# Power.net
KiCad netlist of a schematic drawn in Altium Designer
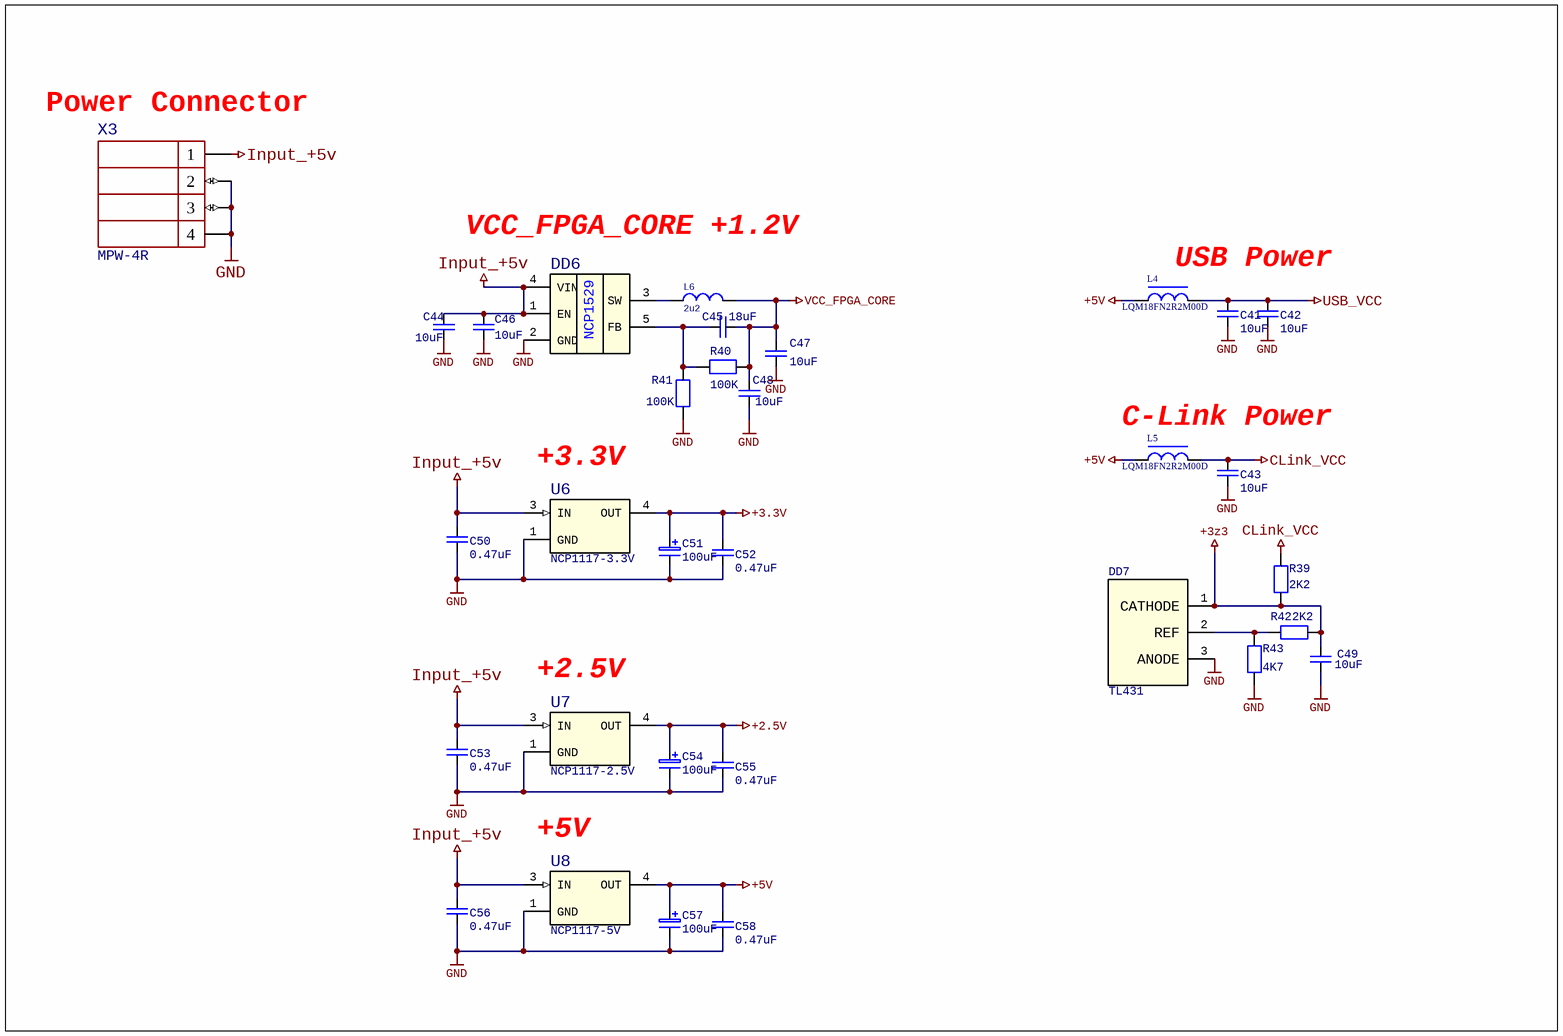
[diagram p0: Power.SchDoc]

(export (version "E")
  (design (tool "Eeschema 10.0.6"))
  (components
    (comp (ref "C41")
      (value "10uF")
      (footprint "Passive:C_0603")
      (description "Non-polarised capacitor")
      (libsource (lib "Passive") (part "C"))
    )
    (comp (ref "C42")
      (value "10uF")
      (footprint "Passive:C_0603")
      (description "Non-polarised capacitor")
      (libsource (lib "Passive") (part "C"))
    )
    (comp (ref "C43")
      (value "10uF")
      (footprint "Passive:C_0603")
      (description "Non-polarised capacitor")
      (libsource (lib "Passive") (part "C"))
    )
    (comp (ref "C44")
      (value "10uF")
      (footprint "Passive:C_0603")
      (description "Non-polarised capacitor")
      (libsource (lib "Passive") (part "C"))
    )
    (comp (ref "C45")
      (value "18uF")
      (footprint "Passive:C_0603")
      (description "Non-polarised capacitor")
      (libsource (lib "Passive") (part "C"))
    )
    (comp (ref "C46")
      (value "10uF")
      (footprint "Passive:C_0603")
      (description "Non-polarised capacitor")
      (libsource (lib "Passive") (part "C"))
    )
    (comp (ref "C47")
      (value "10uF")
      (footprint "Passive:C_0603")
      (description "Non-polarised capacitor")
      (libsource (lib "Passive") (part "C"))
    )
    (comp (ref "C48")
      (value "10uF")
      (footprint "Passive:C_0603")
      (description "Non-polarised capacitor")
      (libsource (lib "Passive") (part "C"))
    )
    (comp (ref "C49")
      (value "10uF")
      (footprint "Passive:C_0603")
      (description "Non-polarised capacitor")
      (libsource (lib "Passive") (part "C"))
    )
    (comp (ref "C50")
      (value "0.47uF")
      (footprint "Passive:C_0603")
      (description "Non-polarised capacitor")
      (libsource (lib "Passive") (part "C"))
    )
    (comp (ref "C51")
      (value "100uF")
      (footprint "Passive:SMD D")
      (description "Polarised capacitor")
      (libsource (lib "Passive") (part "C_polar"))
    )
    (comp (ref "C52")
      (value "0.47uF")
      (footprint "Passive:C_0603")
      (description "Non-polarised capacitor")
      (libsource (lib "Passive") (part "C"))
    )
    (comp (ref "C53")
      (value "0.47uF")
      (footprint "Passive:C_0603")
      (description "Non-polarised capacitor")
      (libsource (lib "Passive") (part "C"))
    )
    (comp (ref "C54")
      (value "100uF")
      (footprint "Passive:SMD D")
      (description "Polarised capacitor")
      (libsource (lib "Passive") (part "C_polar"))
    )
    (comp (ref "C55")
      (value "0.47uF")
      (footprint "Passive:C_0603")
      (description "Non-polarised capacitor")
      (libsource (lib "Passive") (part "C"))
    )
    (comp (ref "C56")
      (value "0.47uF")
      (footprint "Passive:C_0603")
      (description "Non-polarised capacitor")
      (libsource (lib "Passive") (part "C"))
    )
    (comp (ref "C57")
      (value "100uF")
      (footprint "Passive:SMD D")
      (description "Polarised capacitor")
      (libsource (lib "Passive") (part "C_polar"))
    )
    (comp (ref "C58")
      (value "0.47uF")
      (footprint "Passive:C_0603")
      (description "Non-polarised capacitor")
      (libsource (lib "Passive") (part "C"))
    )
    (comp (ref "DD6") (value "NCP1529") (footprint "SOT-23-5") (libsource (lib "Power") (part "NCP1529")))
    (comp (ref "DD7") (value "TL431") (footprint "SOT-23") (libsource (lib "Power") (part "TL431")))
    (comp (ref "L4")
      (value "LQM18FN2R2M00D")
      (footprint "Passive:L_0603")
      (libsource (lib "Passive") (part "L"))
    )
    (comp (ref "L5")
      (value "LQM18FN2R2M00D")
      (footprint "Passive:L_0603")
      (libsource (lib "Passive") (part "L"))
    )
    (comp (ref "L6") (value "2u2") (footprint "Passive:L_1008") (libsource (lib "Passive") (part "L_2")))
    (comp (ref "R39") (value "2K2") (footprint "Passive:R_0603") (libsource (lib "") (part "R_2")))
    (comp (ref "R40") (value "100K") (footprint "Passive:R_0603") (libsource (lib "Passive") (part "R")))
    (comp (ref "R41") (value "100K") (footprint "Passive:R_0603") (libsource (lib "") (part "R_1")))
    (comp (ref "R42") (value "2K2") (footprint "Passive:R_0603") (libsource (lib "Passive") (part "R")))
    (comp (ref "R43") (value "4K7") (footprint "Passive:R_0603") (libsource (lib "") (part "R_1")))
    (comp (ref "U6")
      (value "NCP1117-3.3V")
      (footprint "TO:TO-252")
      (description "1.5 V,1.8 V, 1.9 V, 2.0 V, 2.5 V, 2.85 V, 3.3 V, 5.0 V,12 V")
      (libsource (lib "Device") (part "NCP1117"))
    )
    (comp (ref "U7")
      (value "NCP1117-2.5V")
      (footprint "TO:TO-252")
      (description "1.5 V,1.8 V, 1.9 V, 2.0 V, 2.5 V, 2.85 V, 3.3 V, 5.0 V,12 V")
      (libsource (lib "Device") (part "NCP1117"))
    )
    (comp (ref "U8")
      (value "NCP1117-5V")
      (footprint "TO:TO-252")
      (description "1.5 V,1.8 V, 1.9 V, 2.0 V, 2.5 V, 2.85 V, 3.3 V, 5.0 V,12 V")
      (libsource (lib "Device") (part "NCP1117"))
    )
    (comp (ref "X3")
      (value "MPW-4R")
      (footprint "Connector_Power:MPW-4R")
      (description "Разъемы низковольтного питания")
      (libsource (lib "Power") (part "MPW-4R"))
    )
  )
  (nets
    (net (code "1") (name "+2.5V") (class "Default")
      (node (ref "C54") (pin "1") (pinfunction "1_1") (pintype "passive"))
      (node (ref "C55") (pin "1") (pinfunction "1_1") (pintype "passive"))
      (node (ref "U7") (pin "4") (pinfunction "OUT_4") (pintype "passive"))
    )
    (net (code "2") (name "+3.3V") (class "Default")
      (node (ref "C51") (pin "1") (pinfunction "1_1") (pintype "passive"))
      (node (ref "C52") (pin "1") (pinfunction "1_1") (pintype "passive"))
      (node (ref "U6") (pin "4") (pinfunction "OUT_4") (pintype "passive"))
    )
    (net (code "3") (name "+3z3") (class "Default")
      (node (ref "C49") (pin "1") (pinfunction "1_1") (pintype "passive"))
      (node (ref "DD7") (pin "1") (pinfunction "CATHODE_1") (pintype "passive"))
      (node (ref "R39") (pin "1") (pinfunction "1_1") (pintype "passive"))
      (node (ref "R42") (pin "2") (pinfunction "2_2") (pintype "passive"))
    )
    (net (code "4") (name "+5V") (class "Default")
      (node (ref "C57") (pin "1") (pinfunction "1_1") (pintype "passive"))
      (node (ref "C58") (pin "1") (pinfunction "1_1") (pintype "passive"))
      (node (ref "L4") (pin "1") (pinfunction "1_1") (pintype "passive"))
      (node (ref "L5") (pin "1") (pinfunction "1_1") (pintype "passive"))
      (node (ref "U8") (pin "4") (pinfunction "OUT_4") (pintype "passive"))
    )
    (net (code "5") (name "CLink_VCC") (class "Default")
      (node (ref "C43") (pin "1") (pinfunction "1_1") (pintype "passive"))
      (node (ref "L5") (pin "2") (pinfunction "2_2") (pintype "passive"))
      (node (ref "R39") (pin "2") (pinfunction "2_2") (pintype "passive"))
    )
    (net (code "6") (name "GND") (class "Default")
      (node (ref "C41") (pin "2") (pinfunction "2_2") (pintype "passive"))
      (node (ref "C42") (pin "2") (pinfunction "2_2") (pintype "passive"))
      (node (ref "C43") (pin "2") (pinfunction "2_2") (pintype "passive"))
      (node (ref "C44") (pin "2") (pinfunction "2_2") (pintype "passive"))
      (node (ref "C46") (pin "2") (pinfunction "2_2") (pintype "passive"))
      (node (ref "C47") (pin "1") (pinfunction "1_1") (pintype "passive"))
      (node (ref "C48") (pin "1") (pinfunction "1_1") (pintype "passive"))
      (node (ref "C49") (pin "2") (pinfunction "2_2") (pintype "passive"))
      (node (ref "C50") (pin "2") (pinfunction "2_2") (pintype "passive"))
      (node (ref "C51") (pin "2") (pinfunction "2_2") (pintype "passive"))
      (node (ref "C52") (pin "2") (pinfunction "2_2") (pintype "passive"))
      (node (ref "C53") (pin "2") (pinfunction "2_2") (pintype "passive"))
      (node (ref "C54") (pin "2") (pinfunction "2_2") (pintype "passive"))
      (node (ref "C55") (pin "2") (pinfunction "2_2") (pintype "passive"))
      (node (ref "C56") (pin "2") (pinfunction "2_2") (pintype "passive"))
      (node (ref "C57") (pin "2") (pinfunction "2_2") (pintype "passive"))
      (node (ref "C58") (pin "2") (pinfunction "2_2") (pintype "passive"))
      (node (ref "DD6") (pin "2") (pinfunction "GND_2") (pintype "passive"))
      (node (ref "DD7") (pin "3") (pinfunction "ANODE_3") (pintype "passive"))
      (node (ref "R41") (pin "2") (pinfunction "2_2") (pintype "passive"))
      (node (ref "R43") (pin "2") (pinfunction "2_2") (pintype "passive"))
      (node (ref "U6") (pin "1") (pinfunction "GND_1") (pintype "power_in"))
      (node (ref "U7") (pin "1") (pinfunction "GND_1") (pintype "power_in"))
      (node (ref "U8") (pin "1") (pinfunction "GND_1") (pintype "power_in"))
      (node (ref "X3") (pin "2") (pinfunction "2_2") (pintype "bidirectional"))
      (node (ref "X3") (pin "3") (pinfunction "3_3") (pintype "bidirectional"))
      (node (ref "X3") (pin "4") (pinfunction "4_4") (pintype "passive"))
    )
    (net (code "7") (name "Input_+5v") (class "Default")
      (node (ref "C44") (pin "1") (pinfunction "1_1") (pintype "passive"))
      (node (ref "C46") (pin "1") (pinfunction "1_1") (pintype "passive"))
      (node (ref "C50") (pin "1") (pinfunction "1_1") (pintype "passive"))
      (node (ref "C53") (pin "1") (pinfunction "1_1") (pintype "passive"))
      (node (ref "C56") (pin "1") (pinfunction "1_1") (pintype "passive"))
      (node (ref "DD6") (pin "1") (pinfunction "EN_1") (pintype "passive"))
      (node (ref "DD6") (pin "4") (pinfunction "VIN_4") (pintype "passive"))
      (node (ref "U6") (pin "3") (pinfunction "IN_3") (pintype "input"))
      (node (ref "U7") (pin "3") (pinfunction "IN_3") (pintype "input"))
      (node (ref "U8") (pin "3") (pinfunction "IN_3") (pintype "input"))
      (node (ref "X3") (pin "1") (pinfunction "1_1") (pintype "passive"))
    )
    (net (code "8") (name "Net-(DD6-FB)") (class "Default")
      (node (ref "C45") (pin "1") (pinfunction "1_1") (pintype "passive"))
      (node (ref "DD6") (pin "5") (pinfunction "FB_5") (pintype "passive"))
      (node (ref "R40") (pin "1") (pinfunction "1_1") (pintype "passive"))
      (node (ref "R41") (pin "1") (pinfunction "1_1") (pintype "passive"))
    )
    (net (code "9") (name "Net-(DD6-SW)") (class "Default")
      (node (ref "DD6") (pin "3") (pinfunction "SW_3") (pintype "passive"))
      (node (ref "L6") (pin "1") (pinfunction "1_1") (pintype "passive"))
    )
    (net (code "10") (name "Net-(DD7-REF)") (class "Default")
      (node (ref "DD7") (pin "2") (pinfunction "REF_2") (pintype "passive"))
      (node (ref "R42") (pin "1") (pinfunction "1_1") (pintype "passive"))
      (node (ref "R43") (pin "1") (pinfunction "1_1") (pintype "passive"))
    )
    (net (code "11") (name "USB_VCC") (class "Default")
      (node (ref "C41") (pin "1") (pinfunction "1_1") (pintype "passive"))
      (node (ref "C42") (pin "1") (pinfunction "1_1") (pintype "passive"))
      (node (ref "L4") (pin "2") (pinfunction "2_2") (pintype "passive"))
    )
    (net (code "12") (name "VCC_FPGA_CORE") (class "Default")
      (node (ref "C45") (pin "2") (pinfunction "2_2") (pintype "passive"))
      (node (ref "C47") (pin "2") (pinfunction "2_2") (pintype "passive"))
      (node (ref "C48") (pin "2") (pinfunction "2_2") (pintype "passive"))
      (node (ref "L6") (pin "2") (pinfunction "2_2") (pintype "passive"))
      (node (ref "R40") (pin "2") (pinfunction "2_2") (pintype "passive"))
    )
  )
)
